# Carte_alim.net
KiCad netlist of a schematic drawn in Altium Designer
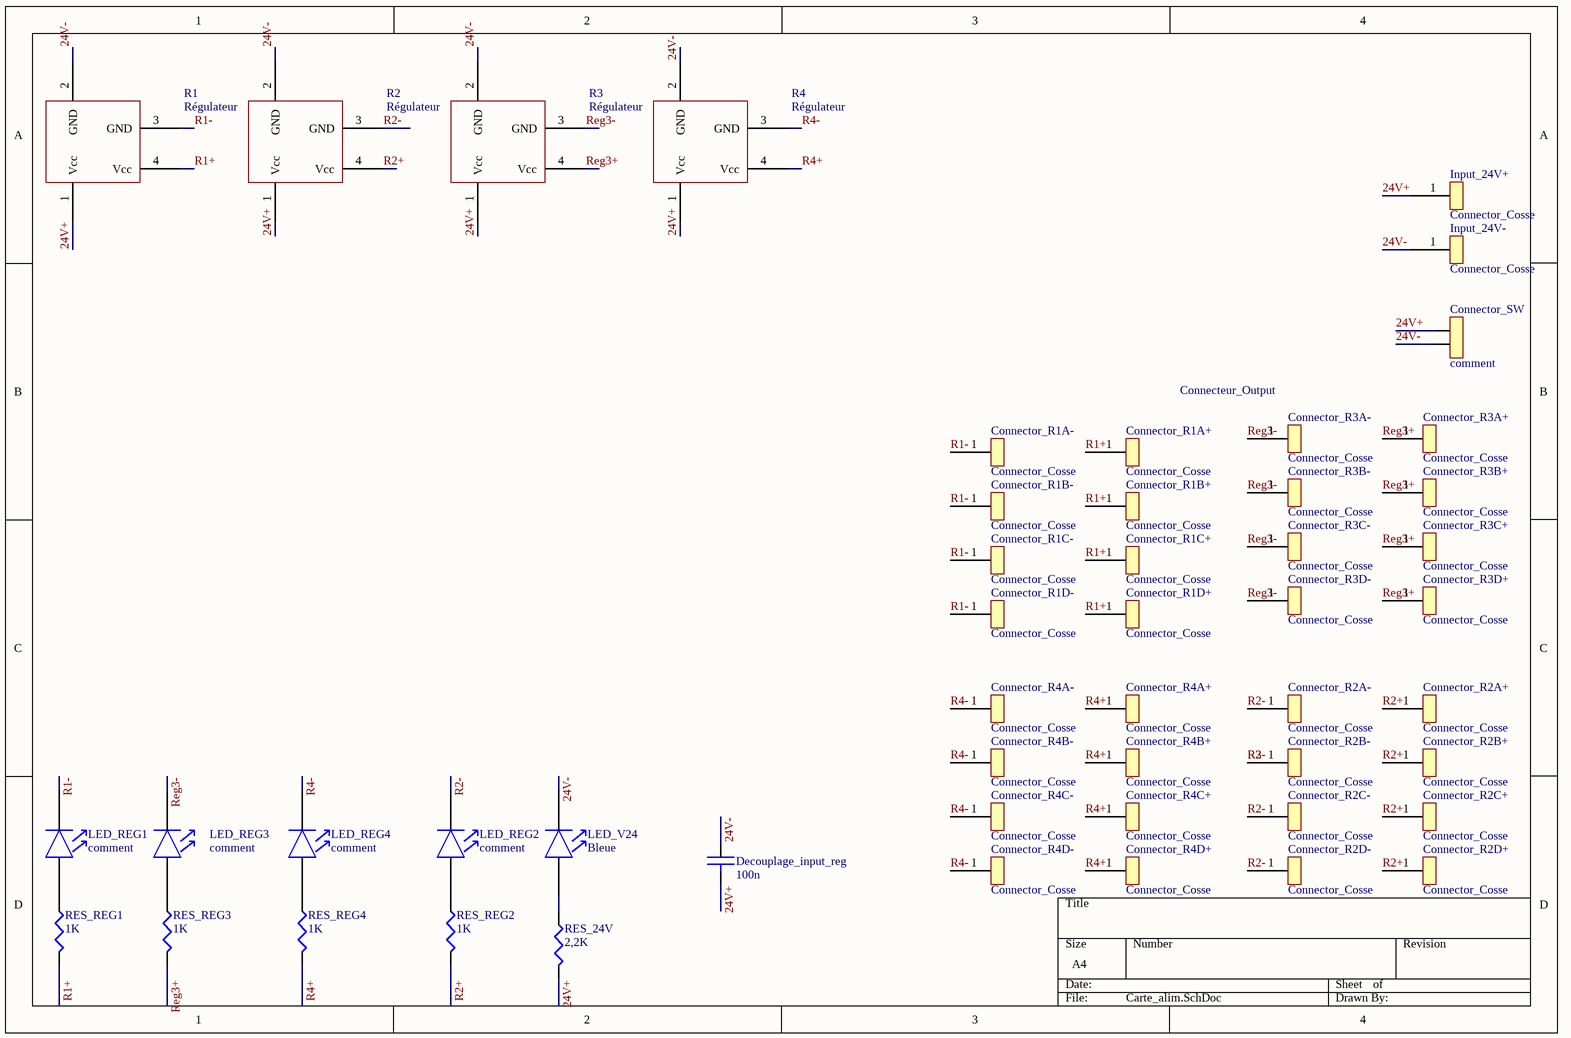
[diagram p0: Carte_alim.SchDoc]

(export (version "E")
  (design (tool "Eeschema 10.0.6"))
  (components
    (comp (ref "Connector_R1A+")
      (value "Connector_Cosse")
      (footprint "Connector_Cosse")
      (libsource (lib "Connector_Cosse") (part "Connector_Cosse"))
    )
    (comp (ref "Connector_R1A-")
      (value "Connector_Cosse")
      (footprint "Connector_Cosse")
      (libsource (lib "Connector_Cosse") (part "Connector_Cosse"))
    )
    (comp (ref "Connector_R1B+")
      (value "Connector_Cosse")
      (footprint "Connector_Cosse")
      (libsource (lib "Connector_Cosse") (part "Connector_Cosse"))
    )
    (comp (ref "Connector_R1B-")
      (value "Connector_Cosse")
      (footprint "Connector_Cosse")
      (libsource (lib "Connector_Cosse") (part "Connector_Cosse"))
    )
    (comp (ref "Connector_R1C+")
      (value "Connector_Cosse")
      (footprint "Connector_Cosse")
      (libsource (lib "Connector_Cosse") (part "Connector_Cosse"))
    )
    (comp (ref "Connector_R1C-")
      (value "Connector_Cosse")
      (footprint "Connector_Cosse")
      (libsource (lib "Connector_Cosse") (part "Connector_Cosse"))
    )
    (comp (ref "Connector_R1D+")
      (value "Connector_Cosse")
      (footprint "Connector_Cosse")
      (libsource (lib "Connector_Cosse") (part "Connector_Cosse"))
    )
    (comp (ref "Connector_R1D-")
      (value "Connector_Cosse")
      (footprint "Connector_Cosse")
      (libsource (lib "Connector_Cosse") (part "Connector_Cosse"))
    )
    (comp (ref "Connector_R2A+")
      (value "Connector_Cosse")
      (footprint "Connector_Cosse")
      (libsource (lib "Connector_Cosse") (part "Connector_Cosse"))
    )
    (comp (ref "Connector_R2A-")
      (value "Connector_Cosse")
      (footprint "Connector_Cosse")
      (libsource (lib "Connector_Cosse") (part "Connector_Cosse"))
    )
    (comp (ref "Connector_R2B+")
      (value "Connector_Cosse")
      (footprint "Connector_Cosse")
      (libsource (lib "Connector_Cosse") (part "Connector_Cosse"))
    )
    (comp (ref "Connector_R2B-")
      (value "Connector_Cosse")
      (footprint "Connector_Cosse")
      (libsource (lib "Connector_Cosse") (part "Connector_Cosse"))
    )
    (comp (ref "Connector_R2C+")
      (value "Connector_Cosse")
      (footprint "Connector_Cosse")
      (libsource (lib "Connector_Cosse") (part "Connector_Cosse"))
    )
    (comp (ref "Connector_R2C-")
      (value "Connector_Cosse")
      (footprint "Connector_Cosse")
      (libsource (lib "Connector_Cosse") (part "Connector_Cosse"))
    )
    (comp (ref "Connector_R2D+")
      (value "Connector_Cosse")
      (footprint "Connector_Cosse")
      (libsource (lib "Connector_Cosse") (part "Connector_Cosse"))
    )
    (comp (ref "Connector_R2D-")
      (value "Connector_Cosse")
      (footprint "Connector_Cosse")
      (libsource (lib "Connector_Cosse") (part "Connector_Cosse"))
    )
    (comp (ref "Connector_R3A+")
      (value "Connector_Cosse")
      (footprint "Connector_Cosse")
      (libsource (lib "Connector_Cosse") (part "Connector_Cosse"))
    )
    (comp (ref "Connector_R3A-")
      (value "Connector_Cosse")
      (footprint "Connector_Cosse")
      (libsource (lib "Connector_Cosse") (part "Connector_Cosse"))
    )
    (comp (ref "Connector_R3B+")
      (value "Connector_Cosse")
      (footprint "Connector_Cosse")
      (libsource (lib "Connector_Cosse") (part "Connector_Cosse"))
    )
    (comp (ref "Connector_R3B-")
      (value "Connector_Cosse")
      (footprint "Connector_Cosse")
      (libsource (lib "Connector_Cosse") (part "Connector_Cosse"))
    )
    (comp (ref "Connector_R3C+")
      (value "Connector_Cosse")
      (footprint "Connector_Cosse")
      (libsource (lib "Connector_Cosse") (part "Connector_Cosse"))
    )
    (comp (ref "Connector_R3C-")
      (value "Connector_Cosse")
      (footprint "Connector_Cosse")
      (libsource (lib "Connector_Cosse") (part "Connector_Cosse"))
    )
    (comp (ref "Connector_R3D+")
      (value "Connector_Cosse")
      (footprint "Connector_Cosse")
      (libsource (lib "Connector_Cosse") (part "Connector_Cosse"))
    )
    (comp (ref "Connector_R3D-")
      (value "Connector_Cosse")
      (footprint "Connector_Cosse")
      (libsource (lib "Connector_Cosse") (part "Connector_Cosse"))
    )
    (comp (ref "Connector_R4A+")
      (value "Connector_Cosse")
      (footprint "Connector_Cosse")
      (libsource (lib "Connector_Cosse") (part "Connector_Cosse"))
    )
    (comp (ref "Connector_R4A-")
      (value "Connector_Cosse")
      (footprint "Connector_Cosse")
      (libsource (lib "Connector_Cosse") (part "Connector_Cosse"))
    )
    (comp (ref "Connector_R4B+")
      (value "Connector_Cosse")
      (footprint "Connector_Cosse")
      (libsource (lib "Connector_Cosse") (part "Connector_Cosse"))
    )
    (comp (ref "Connector_R4B-")
      (value "Connector_Cosse")
      (footprint "Connector_Cosse")
      (libsource (lib "Connector_Cosse") (part "Connector_Cosse"))
    )
    (comp (ref "Connector_R4C+")
      (value "Connector_Cosse")
      (footprint "Connector_Cosse")
      (libsource (lib "Connector_Cosse") (part "Connector_Cosse"))
    )
    (comp (ref "Connector_R4C-")
      (value "Connector_Cosse")
      (footprint "Connector_Cosse")
      (libsource (lib "Connector_Cosse") (part "Connector_Cosse"))
    )
    (comp (ref "Connector_R4D+")
      (value "Connector_Cosse")
      (footprint "Connector_Cosse")
      (libsource (lib "Connector_Cosse") (part "Connector_Cosse"))
    )
    (comp (ref "Connector_R4D-")
      (value "Connector_Cosse")
      (footprint "Connector_Cosse")
      (libsource (lib "Connector_Cosse") (part "Connector_Cosse"))
    )
    (comp (ref "Connector_SW")
      (value "comment")
      (footprint "AMP_2")
      (description "connecteur alim 2 pôles")
      (libsource (lib "ISEN_basics") (part "POWER2"))
    )
    (comp (ref "Decouplage_input_reg")
      (value "100n")
      (footprint "0805")
      (description "capacité non polarisée")
      (fields (field (name "Comment") "CAP"))
      (libsource (lib "ISEN_basics") (part "CAP"))
    )
    (comp (ref "Input_24V+")
      (value "Connector_Cosse")
      (footprint "Connector_Cosse")
      (libsource (lib "Connector_Cosse") (part "Connector_Cosse"))
    )
    (comp (ref "Input_24V-")
      (value "Connector_Cosse")
      (footprint "Connector_Cosse")
      (libsource (lib "Connector_Cosse") (part "Connector_Cosse"))
    )
    (comp (ref "LED_REG1")
      (value "comment")
      (footprint "LED0805")
      (description "LED 5mm/3mm/CMS")
      (libsource (lib "ISEN_basics") (part "LED"))
    )
    (comp (ref "LED_REG2")
      (value "comment")
      (footprint "LED0805")
      (description "LED 5mm/3mm/CMS")
      (libsource (lib "ISEN_basics") (part "LED"))
    )
    (comp (ref "LED_REG3")
      (value "comment")
      (footprint "LED0805")
      (description "LED 5mm/3mm/CMS")
      (libsource (lib "ISEN_basics") (part "LED"))
    )
    (comp (ref "LED_REG4")
      (value "comment")
      (footprint "LED0805")
      (description "LED 5mm/3mm/CMS")
      (libsource (lib "ISEN_basics") (part "LED"))
    )
    (comp (ref "LED_V24")
      (value "Bleue")
      (footprint "LED0805")
      (description "LED 5mm/3mm/CMS")
      (libsource (lib "ISEN_basics") (part "LED"))
    )
    (comp (ref "R1")
      (value "Régulateur")
      (footprint "Régulateur")
      (description "Régulateur de tension")
      (libsource (lib "Schlib1") (part "Régulateur"))
    )
    (comp (ref "R2")
      (value "Régulateur")
      (footprint "Régulateur")
      (description "Régulateur de tension")
      (libsource (lib "Schlib1") (part "Régulateur"))
    )
    (comp (ref "R3")
      (value "Régulateur")
      (footprint "Régulateur")
      (description "Régulateur de tension")
      (libsource (lib "Regulateur_Tension") (part "Régulateur"))
    )
    (comp (ref "R4")
      (value "Régulateur")
      (footprint "Régulateur")
      (description "Régulateur de tension")
      (libsource (lib "Schlib1") (part "Régulateur"))
    )
    (comp (ref "RES_24V")
      (value "2,2K")
      (footprint "0805")
      (description "resistance")
      (libsource (lib "ISEN_basics") (part "RES"))
    )
    (comp (ref "RES_REG1")
      (value "1K")
      (footprint "0805")
      (description "resistance")
      (fields (field (name "Comment") "RES"))
      (libsource (lib "ISEN_basics") (part "RES"))
    )
    (comp (ref "RES_REG2")
      (value "1K")
      (footprint "0805")
      (description "resistance")
      (fields (field (name "Comment") "RES"))
      (libsource (lib "ISEN_basics") (part "RES"))
    )
    (comp (ref "RES_REG3")
      (value "1K")
      (footprint "0805")
      (description "resistance")
      (fields (field (name "Comment") "RES"))
      (libsource (lib "ISEN_basics") (part "RES"))
    )
    (comp (ref "RES_REG4")
      (value "1K")
      (footprint "0805")
      (description "resistance")
      (fields (field (name "Comment") "RES"))
      (libsource (lib "ISEN_basics") (part "RES"))
    )
  )
  (nets
    (net (code "1") (name "/24V+") (class "Default")
      (node (ref "Connector_SW") (pin "2") (pintype "passive"))
      (node (ref "Decouplage_input_reg") (pin "2") (pinfunction "2_2") (pintype "passive"))
      (node (ref "Input_24V+") (pin "1") (pintype "passive"))
      (node (ref "R1") (pin "1") (pinfunction "Vcc_1") (pintype "open_emitter"))
      (node (ref "R2") (pin "1") (pinfunction "Vcc_1") (pintype "open_emitter"))
      (node (ref "R3") (pin "1") (pinfunction "Vcc_1") (pintype "open_emitter"))
      (node (ref "R4") (pin "1") (pinfunction "Vcc_1") (pintype "open_emitter"))
      (node (ref "RES_24V") (pin "2") (pintype "passive"))
    )
    (net (code "2") (name "/24V-") (class "Default")
      (node (ref "Connector_SW") (pin "1") (pintype "passive"))
      (node (ref "Decouplage_input_reg") (pin "1") (pinfunction "1_1") (pintype "passive"))
      (node (ref "Input_24V-") (pin "1") (pintype "passive"))
      (node (ref "LED_V24") (pin "K") (pinfunction "10_K") (pintype "passive"))
      (node (ref "R1") (pin "2") (pinfunction "GND_2") (pintype "power_in"))
      (node (ref "R2") (pin "2") (pinfunction "GND_2") (pintype "power_in"))
      (node (ref "R3") (pin "2") (pinfunction "GND_2") (pintype "power_in"))
      (node (ref "R4") (pin "2") (pinfunction "GND_2") (pintype "power_in"))
    )
    (net (code "3") (name "/R1+") (class "Default")
      (node (ref "Connector_R1A+") (pin "1") (pintype "passive"))
      (node (ref "Connector_R1B+") (pin "1") (pintype "passive"))
      (node (ref "Connector_R1C+") (pin "1") (pintype "passive"))
      (node (ref "Connector_R1D+") (pin "1") (pintype "passive"))
      (node (ref "R1") (pin "4") (pinfunction "Vcc_4") (pintype "power_in"))
      (node (ref "RES_REG1") (pin "2") (pintype "passive"))
    )
    (net (code "4") (name "/R1-") (class "Default")
      (node (ref "Connector_R1A-") (pin "1") (pintype "passive"))
      (node (ref "Connector_R1B-") (pin "1") (pintype "passive"))
      (node (ref "Connector_R1C-") (pin "1") (pintype "passive"))
      (node (ref "Connector_R1D-") (pin "1") (pintype "passive"))
      (node (ref "LED_REG1") (pin "K") (pinfunction "10_K") (pintype "passive"))
      (node (ref "R1") (pin "3") (pinfunction "GND_3") (pintype "power_in"))
    )
    (net (code "5") (name "/R2+") (class "Default")
      (node (ref "Connector_R2A+") (pin "1") (pintype "passive"))
      (node (ref "Connector_R2B+") (pin "1") (pintype "passive"))
      (node (ref "Connector_R2C+") (pin "1") (pintype "passive"))
      (node (ref "Connector_R2D+") (pin "1") (pintype "passive"))
      (node (ref "R2") (pin "4") (pinfunction "Vcc_4") (pintype "power_in"))
      (node (ref "RES_REG2") (pin "2") (pintype "passive"))
    )
    (net (code "6") (name "/R2-") (class "Default")
      (node (ref "Connector_R2A-") (pin "1") (pintype "passive"))
      (node (ref "Connector_R2B-") (pin "1") (pintype "passive"))
      (node (ref "Connector_R2C-") (pin "1") (pintype "passive"))
      (node (ref "Connector_R2D-") (pin "1") (pintype "passive"))
      (node (ref "LED_REG2") (pin "K") (pinfunction "10_K") (pintype "passive"))
      (node (ref "R2") (pin "3") (pinfunction "GND_3") (pintype "power_in"))
    )
    (net (code "7") (name "/R4+") (class "Default")
      (node (ref "Connector_R4A+") (pin "1") (pintype "passive"))
      (node (ref "Connector_R4B+") (pin "1") (pintype "passive"))
      (node (ref "Connector_R4C+") (pin "1") (pintype "passive"))
      (node (ref "Connector_R4D+") (pin "1") (pintype "passive"))
      (node (ref "R4") (pin "4") (pinfunction "Vcc_4") (pintype "power_in"))
      (node (ref "RES_REG4") (pin "2") (pintype "passive"))
    )
    (net (code "8") (name "/R4-") (class "Default")
      (node (ref "Connector_R4A-") (pin "1") (pintype "passive"))
      (node (ref "Connector_R4B-") (pin "1") (pintype "passive"))
      (node (ref "Connector_R4C-") (pin "1") (pintype "passive"))
      (node (ref "Connector_R4D-") (pin "1") (pintype "passive"))
      (node (ref "LED_REG4") (pin "K") (pinfunction "10_K") (pintype "passive"))
      (node (ref "R4") (pin "3") (pinfunction "GND_3") (pintype "power_in"))
    )
    (net (code "9") (name "/Reg3+") (class "Default")
      (node (ref "Connector_R3A+") (pin "1") (pintype "passive"))
      (node (ref "Connector_R3B+") (pin "1") (pintype "passive"))
      (node (ref "Connector_R3C+") (pin "1") (pintype "passive"))
      (node (ref "Connector_R3D+") (pin "1") (pintype "passive"))
      (node (ref "R3") (pin "4") (pinfunction "Vcc_4") (pintype "power_in"))
      (node (ref "RES_REG3") (pin "2") (pintype "passive"))
    )
    (net (code "10") (name "/Reg3-") (class "Default")
      (node (ref "Connector_R3A-") (pin "1") (pintype "passive"))
      (node (ref "Connector_R3B-") (pin "1") (pintype "passive"))
      (node (ref "Connector_R3C-") (pin "1") (pintype "passive"))
      (node (ref "Connector_R3D-") (pin "1") (pintype "passive"))
      (node (ref "LED_REG3") (pin "K") (pinfunction "10_K") (pintype "passive"))
      (node (ref "R3") (pin "3") (pinfunction "GND_3") (pintype "power_in"))
    )
    (net (code "11") (name "Net-(LED_REG1-8)") (class "Default")
      (node (ref "LED_REG1") (pin "A") (pinfunction "8_A") (pintype "passive"))
      (node (ref "RES_REG1") (pin "1") (pintype "passive"))
    )
    (net (code "12") (name "Net-(LED_REG2-8)") (class "Default")
      (node (ref "LED_REG2") (pin "A") (pinfunction "8_A") (pintype "passive"))
      (node (ref "RES_REG2") (pin "1") (pintype "passive"))
    )
    (net (code "13") (name "Net-(LED_REG3-8)") (class "Default")
      (node (ref "LED_REG3") (pin "A") (pinfunction "8_A") (pintype "passive"))
      (node (ref "RES_REG3") (pin "1") (pintype "passive"))
    )
    (net (code "14") (name "Net-(LED_REG4-8)") (class "Default")
      (node (ref "LED_REG4") (pin "A") (pinfunction "8_A") (pintype "passive"))
      (node (ref "RES_REG4") (pin "1") (pintype "passive"))
    )
    (net (code "15") (name "Net-(LED_V24-8)") (class "Default")
      (node (ref "LED_V24") (pin "A") (pinfunction "8_A") (pintype "passive"))
      (node (ref "RES_24V") (pin "1") (pintype "passive"))
    )
  )
)
